# quadruped.net
KiCad netlist of a schematic drawn in EAGLE
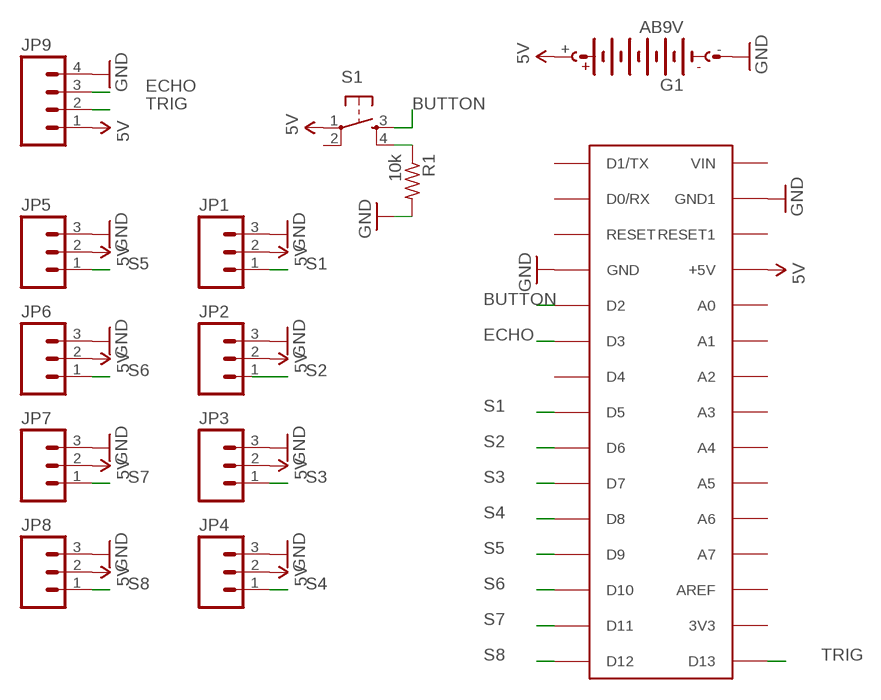
[diagram p0: schematic, sheet 1]

(export (version "E")
  (design (tool "Eeschema 10.0.6"))
  (components
    (comp (ref "G1")
      (value "AB9V")
      (footprint "eagle-import:AB9V")
      (libsource (lib "eagle-import") (part "AB9V"))
    )
    (comp (ref "JP1")
      (value "M03PTH")
      (footprint "eagle-import:1X03")
      (libsource (lib "eagle-import") (part "M03PTH"))
    )
    (comp (ref "JP2")
      (value "M03PTH")
      (footprint "eagle-import:1X03")
      (libsource (lib "eagle-import") (part "M03PTH"))
    )
    (comp (ref "JP3")
      (value "M03PTH")
      (footprint "eagle-import:1X03")
      (libsource (lib "eagle-import") (part "M03PTH"))
    )
    (comp (ref "JP4")
      (value "M03PTH")
      (footprint "eagle-import:1X03")
      (libsource (lib "eagle-import") (part "M03PTH"))
    )
    (comp (ref "JP5")
      (value "M03PTH")
      (footprint "eagle-import:1X03")
      (libsource (lib "eagle-import") (part "M03PTH"))
    )
    (comp (ref "JP6")
      (value "M03PTH")
      (footprint "eagle-import:1X03")
      (libsource (lib "eagle-import") (part "M03PTH"))
    )
    (comp (ref "JP7")
      (value "M03PTH")
      (footprint "eagle-import:1X03")
      (libsource (lib "eagle-import") (part "M03PTH"))
    )
    (comp (ref "JP8")
      (value "M03PTH")
      (footprint "eagle-import:1X03")
      (libsource (lib "eagle-import") (part "M03PTH"))
    )
    (comp (ref "JP9")
      (value "M04PTH")
      (footprint "eagle-import:1X04")
      (libsource (lib "eagle-import") (part "M04PTH"))
    )
    (comp (ref "R1")
      (value "10k")
      (footprint "eagle-import:0204_7")
      (libsource (lib "eagle-import") (part "R-US_0204/7"))
    )
    (comp (ref "S1")
      (value "TAC_SWITCHPTH")
      (footprint "eagle-import:TACTILE-PTH")
      (libsource (lib "eagle-import") (part "TAC_SWITCHPTH"))
    )
    (comp (ref "U$1")
      (value "ARDUINONANO")
      (footprint "eagle-import:PDIP-32")
      (libsource (lib "eagle-import") (part "ARDUINONANO"))
    )
  )
  (nets
    (net (code "1") (name "/BUTTON") (class "Default")
      (node (ref "S1") (pin "3") (pinfunction "3_3") (pintype "passive"))
      (node (ref "U$1") (pin "D2") (pinfunction "D2_D2") (pintype "bidirectional"))
    )
    (net (code "2") (name "/ECHO") (class "Default")
      (node (ref "JP9") (pin "3") (pinfunction "3_3") (pintype "passive"))
      (node (ref "U$1") (pin "D3") (pinfunction "D3_D3") (pintype "bidirectional"))
    )
    (net (code "3") (name "/S1") (class "Default")
      (node (ref "JP1") (pin "1") (pinfunction "1_1") (pintype "passive"))
      (node (ref "U$1") (pin "D5") (pinfunction "D5_D5") (pintype "bidirectional"))
    )
    (net (code "4") (name "/S2") (class "Default")
      (node (ref "JP2") (pin "1") (pinfunction "1_1") (pintype "passive"))
      (node (ref "U$1") (pin "D6") (pinfunction "D6_D6") (pintype "bidirectional"))
    )
    (net (code "5") (name "/S3") (class "Default")
      (node (ref "JP3") (pin "1") (pinfunction "1_1") (pintype "passive"))
      (node (ref "U$1") (pin "D7") (pinfunction "D7_D7") (pintype "bidirectional"))
    )
    (net (code "6") (name "/S4") (class "Default")
      (node (ref "JP4") (pin "1") (pinfunction "1_1") (pintype "passive"))
      (node (ref "U$1") (pin "D8") (pinfunction "D8_D8") (pintype "bidirectional"))
    )
    (net (code "7") (name "/S5") (class "Default")
      (node (ref "JP5") (pin "1") (pinfunction "1_1") (pintype "passive"))
      (node (ref "U$1") (pin "D9") (pinfunction "D9_D9") (pintype "bidirectional"))
    )
    (net (code "8") (name "/S6") (class "Default")
      (node (ref "JP6") (pin "1") (pinfunction "1_1") (pintype "passive"))
      (node (ref "U$1") (pin "D10") (pinfunction "D10_D10") (pintype "bidirectional"))
    )
    (net (code "9") (name "/S7") (class "Default")
      (node (ref "JP7") (pin "1") (pinfunction "1_1") (pintype "passive"))
      (node (ref "U$1") (pin "D11") (pinfunction "D11_D11") (pintype "bidirectional"))
    )
    (net (code "10") (name "/S8") (class "Default")
      (node (ref "JP8") (pin "1") (pinfunction "1_1") (pintype "passive"))
      (node (ref "U$1") (pin "D12") (pinfunction "D12_D12") (pintype "bidirectional"))
    )
    (net (code "11") (name "/TRIG") (class "Default")
      (node (ref "JP9") (pin "2") (pinfunction "2_2") (pintype "passive"))
      (node (ref "U$1") (pin "D13") (pinfunction "D13_D13") (pintype "bidirectional"))
    )
    (net (code "12") (name "5V") (class "Default")
      (node (ref "G1") (pin "+") (pinfunction "+_+") (pintype "passive"))
      (node (ref "JP1") (pin "2") (pinfunction "2_2") (pintype "passive"))
      (node (ref "JP2") (pin "2") (pinfunction "2_2") (pintype "passive"))
      (node (ref "JP3") (pin "2") (pinfunction "2_2") (pintype "passive"))
      (node (ref "JP4") (pin "2") (pinfunction "2_2") (pintype "passive"))
      (node (ref "JP5") (pin "2") (pinfunction "2_2") (pintype "passive"))
      (node (ref "JP6") (pin "2") (pinfunction "2_2") (pintype "passive"))
      (node (ref "JP7") (pin "2") (pinfunction "2_2") (pintype "passive"))
      (node (ref "JP8") (pin "2") (pinfunction "2_2") (pintype "passive"))
      (node (ref "JP9") (pin "1") (pinfunction "1_1") (pintype "passive"))
      (node (ref "S1") (pin "1") (pinfunction "1_1") (pintype "passive"))
      (node (ref "U$1") (pin "+5V") (pinfunction "+5V_+5V") (pintype "bidirectional"))
    )
    (net (code "13") (name "GND") (class "Default")
      (node (ref "G1") (pin "-") (pinfunction "-_-") (pintype "passive"))
      (node (ref "JP1") (pin "3") (pinfunction "3_3") (pintype "passive"))
      (node (ref "JP2") (pin "3") (pinfunction "3_3") (pintype "passive"))
      (node (ref "JP3") (pin "3") (pinfunction "3_3") (pintype "passive"))
      (node (ref "JP4") (pin "3") (pinfunction "3_3") (pintype "passive"))
      (node (ref "JP5") (pin "3") (pinfunction "3_3") (pintype "passive"))
      (node (ref "JP6") (pin "3") (pinfunction "3_3") (pintype "passive"))
      (node (ref "JP7") (pin "3") (pinfunction "3_3") (pintype "passive"))
      (node (ref "JP8") (pin "3") (pinfunction "3_3") (pintype "passive"))
      (node (ref "JP9") (pin "4") (pinfunction "4_4") (pintype "passive"))
      (node (ref "R1") (pin "2") (pinfunction "2_2") (pintype "passive"))
      (node (ref "U$1") (pin "GND") (pinfunction "GND_GND") (pintype "bidirectional"))
      (node (ref "U$1") (pin "GND1") (pinfunction "GND1_GND1") (pintype "bidirectional"))
    )
    (net (code "14") (name "Net-(R1-Pad1)") (class "Default")
      (node (ref "R1") (pin "1") (pinfunction "1_1") (pintype "passive"))
      (node (ref "S1") (pin "4") (pinfunction "4_4") (pintype "passive"))
    )
    (net (code "15") (name "unconnected-(S1-Pad2)") (class "Default")
      (node (ref "S1") (pin "2") (pinfunction "2_2") (pintype "passive"))
    )
    (net (code "16") (name "unconnected-(U$1-Pad3V3)") (class "Default")
      (node (ref "U$1") (pin "3V3") (pinfunction "3V3_3V3") (pintype "bidirectional"))
    )
    (net (code "17") (name "unconnected-(U$1-PadA0)") (class "Default")
      (node (ref "U$1") (pin "A0") (pinfunction "A0_A0") (pintype "bidirectional"))
    )
    (net (code "18") (name "unconnected-(U$1-PadA1)") (class "Default")
      (node (ref "U$1") (pin "A1") (pinfunction "A1_A1") (pintype "bidirectional"))
    )
    (net (code "19") (name "unconnected-(U$1-PadA2)") (class "Default")
      (node (ref "U$1") (pin "A2") (pinfunction "A2_A2") (pintype "bidirectional"))
    )
    (net (code "20") (name "unconnected-(U$1-PadA3)") (class "Default")
      (node (ref "U$1") (pin "A3") (pinfunction "A3_A3") (pintype "bidirectional"))
    )
    (net (code "21") (name "unconnected-(U$1-PadA4)") (class "Default")
      (node (ref "U$1") (pin "A4") (pinfunction "A4_A4") (pintype "bidirectional"))
    )
    (net (code "22") (name "unconnected-(U$1-PadA5)") (class "Default")
      (node (ref "U$1") (pin "A5") (pinfunction "A5_A5") (pintype "bidirectional"))
    )
    (net (code "23") (name "unconnected-(U$1-PadA6)") (class "Default")
      (node (ref "U$1") (pin "A6") (pinfunction "A6_A6") (pintype "bidirectional"))
    )
    (net (code "24") (name "unconnected-(U$1-PadA7)") (class "Default")
      (node (ref "U$1") (pin "A7") (pinfunction "A7_A7") (pintype "bidirectional"))
    )
    (net (code "25") (name "unconnected-(U$1-PadAREF)") (class "Default")
      (node (ref "U$1") (pin "AREF") (pinfunction "AREF_AREF") (pintype "bidirectional"))
    )
    (net (code "26") (name "unconnected-(U$1-PadD0{slash}RX)") (class "Default")
      (node (ref "U$1") (pin "D0/RX") (pinfunction "D0/RX_D0/RX") (pintype "bidirectional"))
    )
    (net (code "27") (name "unconnected-(U$1-PadD1{slash}TX)") (class "Default")
      (node (ref "U$1") (pin "D1/TX") (pinfunction "D1/TX_D1/TX") (pintype "bidirectional"))
    )
    (net (code "28") (name "unconnected-(U$1-PadD4)") (class "Default")
      (node (ref "U$1") (pin "D4") (pinfunction "D4_D4") (pintype "bidirectional"))
    )
    (net (code "29") (name "unconnected-(U$1-PadRESET)") (class "Default")
      (node (ref "U$1") (pin "RESET") (pinfunction "RESET_RESET") (pintype "bidirectional"))
    )
    (net (code "30") (name "unconnected-(U$1-PadRESET1)") (class "Default")
      (node (ref "U$1") (pin "RESET1") (pinfunction "RESET1_RESET1") (pintype "bidirectional"))
    )
    (net (code "31") (name "unconnected-(U$1-PadVIN)") (class "Default")
      (node (ref "U$1") (pin "VIN") (pinfunction "VIN_VIN") (pintype "bidirectional"))
    )
  )
)
